# SparkFun_Qwiic_ESLOV_Adapter.net
KiCad netlist of a schematic drawn in EAGLE
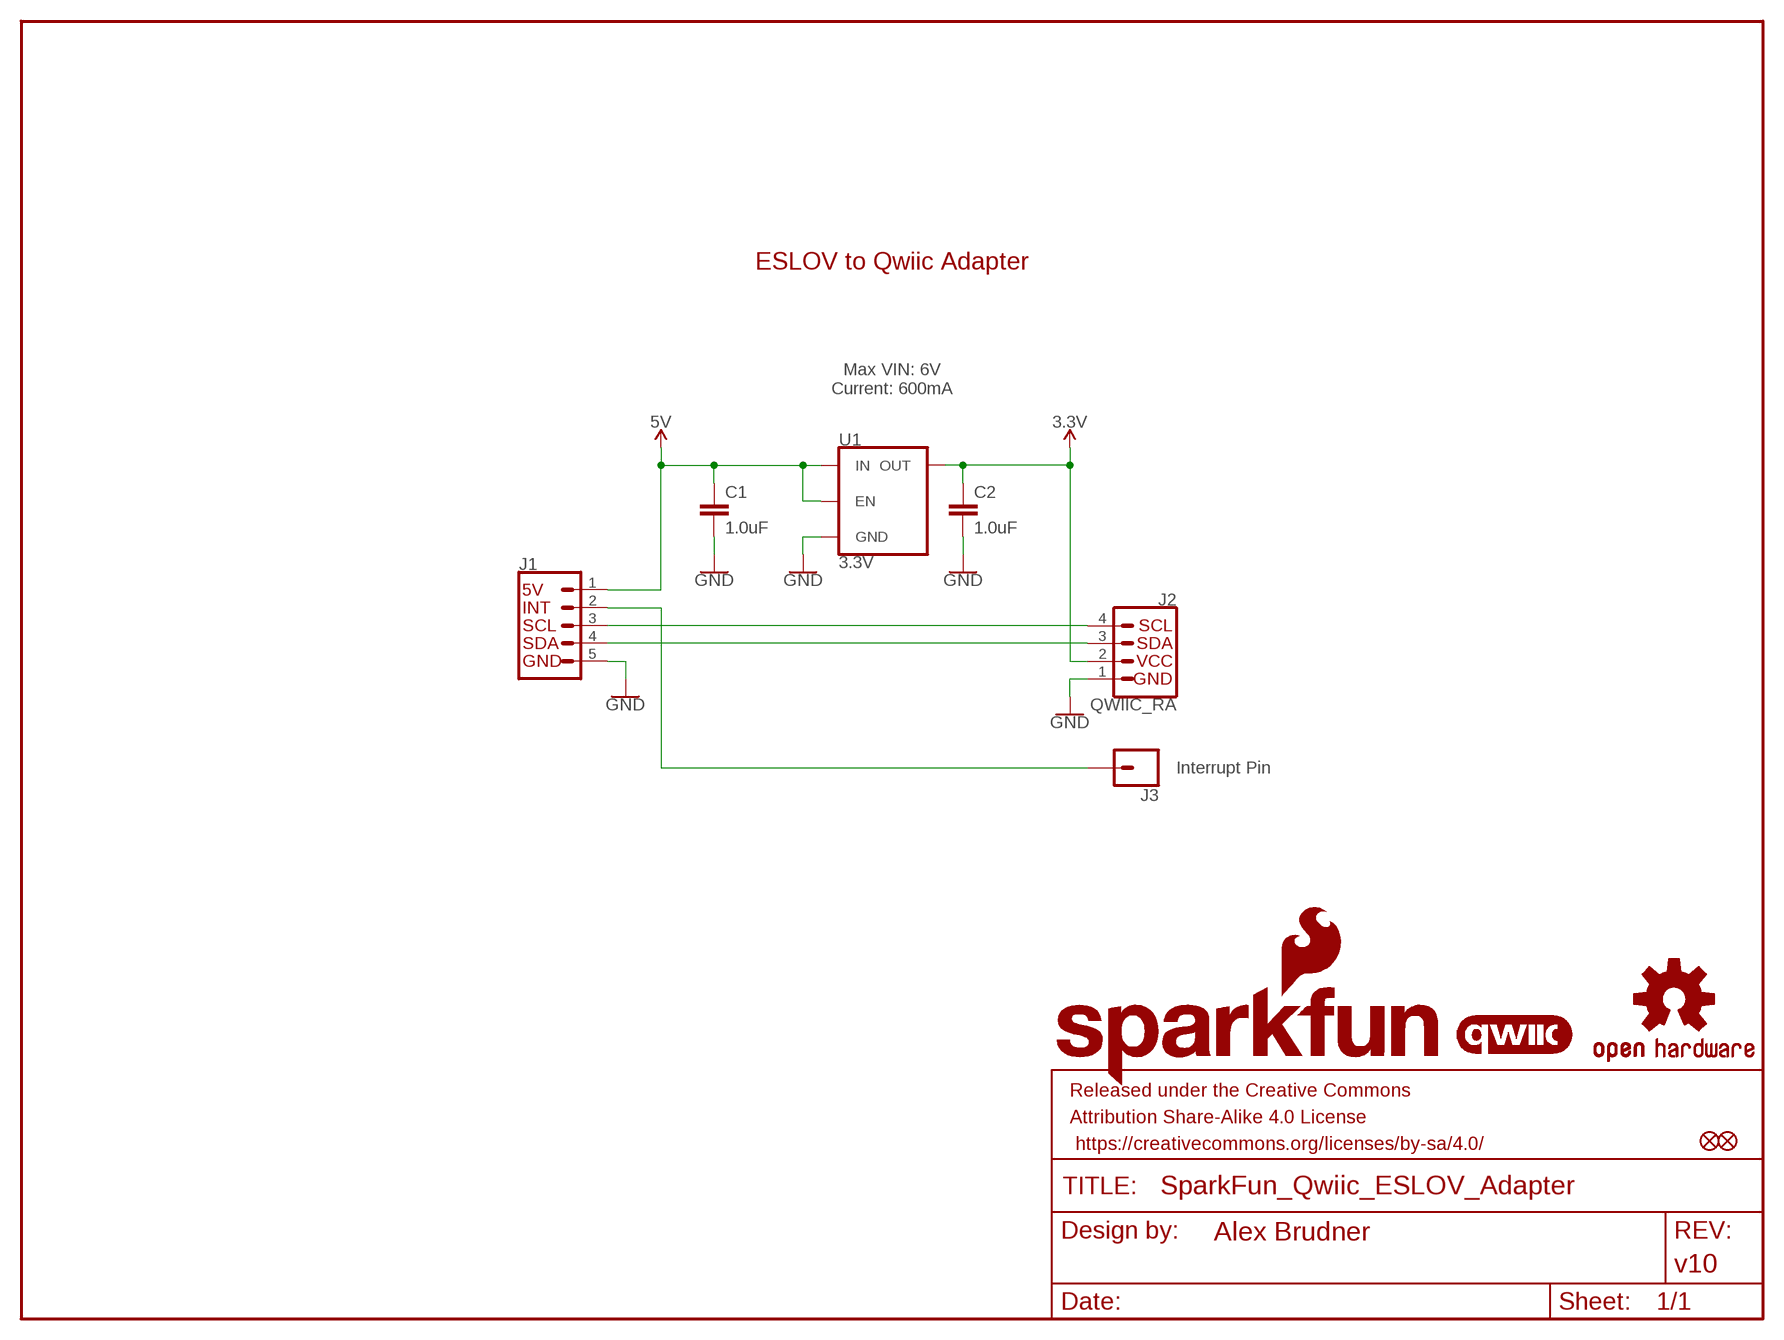
[diagram p0: schematic, sheet 1]

(export (version "E")
  (design (tool "Eeschema 10.0.6"))
  (components
    (comp (ref "C1")
      (value "1.0uF")
      (footprint "eagle-import:0402-TIGHT")
      (libsource (lib "eagle-import") (part "1.0UF-0402T-16V-10%"))
    )
    (comp (ref "C2")
      (value "1.0uF")
      (footprint "eagle-import:0402-TIGHT")
      (libsource (lib "eagle-import") (part "1.0UF-0402T-16V-10%"))
    )
    (comp (ref "FD1")
      (value "FIDUCIALUFIDUCIAL")
      (footprint "eagle-import:FIDUCIAL-MICRO")
      (libsource (lib "eagle-import") (part "FIDUCIALUFIDUCIAL"))
    )
    (comp (ref "FD2")
      (value "FIDUCIALUFIDUCIAL")
      (footprint "eagle-import:FIDUCIAL-MICRO")
      (libsource (lib "eagle-import") (part "FIDUCIALUFIDUCIAL"))
    )
    (comp (ref "FRAME1")
      (value "FRAME-LETTER")
      (footprint "eagle-import:CREATIVE_COMMONS")
      (fields (field (name "DESIGNER") "Alex Brudner") (field (name "REV") "v10"))
      (libsource (lib "eagle-import") (part "FRAME-LETTER"))
    )
    (comp (ref "J1")
      (value "ESLOV")
      (footprint "eagle-import:JST_5_1MM_RA")
      (libsource (lib "eagle-import") (part "ESLOV"))
    )
    (comp (ref "J2")
      (value "QWIIC_RA")
      (footprint "eagle-import:JST04_1MM_RA")
      (libsource (lib "eagle-import") (part "QWIIC_CONNECTORJS-1MM"))
    )
    (comp (ref "J3")
      (value "CONN_01")
      (footprint "eagle-import:1X01")
      (libsource (lib "eagle-import") (part "CONN_01"))
    )
    (comp (ref "LOGO1")
      (value "SFE_LOGO_NAME_FLAME.1_INCH")
      (footprint "eagle-import:SFE_LOGO_NAME_FLAME_.1")
      (libsource (lib "eagle-import") (part "SFE_LOGO_NAME_FLAME.1_INCH"))
    )
    (comp (ref "LOGO2")
      (value "OSHW-LOGOMINI")
      (footprint "eagle-import:OSHW-LOGO-MINI")
      (libsource (lib "eagle-import") (part "OSHW-LOGOMINI"))
    )
    (comp (ref "LOGO3")
      (value "QWIIC_LOGO_CONNECTOR")
      (footprint "eagle-import:QWIIC_5.5MM")
      (libsource (lib "eagle-import") (part "QWIIC_LOGO_CONNECTOR"))
    )
    (comp (ref "U1")
      (value "3.3V")
      (footprint "eagle-import:SOT23-5")
      (libsource (lib "eagle-import") (part "V_REG_AP2112K-3.3V"))
    )
  )
  (nets
    (net (code "1") (name "3.3V") (class "Default")
      (node (ref "C2") (pin "1") (pinfunction "1_1") (pintype "passive"))
      (node (ref "J2") (pin "2") (pinfunction "2_2") (pintype "power_in"))
      (node (ref "U1") (pin "5") (pinfunction "OUT_5") (pintype "passive"))
    )
    (net (code "2") (name "5V") (class "Default")
      (node (ref "C1") (pin "1") (pinfunction "1_1") (pintype "passive"))
      (node (ref "J1") (pin "1") (pinfunction "1_1") (pintype "power_in"))
      (node (ref "U1") (pin "1") (pinfunction "IN_1") (pintype "input"))
      (node (ref "U1") (pin "3") (pinfunction "EN_3") (pintype "input"))
    )
    (net (code "3") (name "GND") (class "Default")
      (node (ref "C1") (pin "2") (pinfunction "2_2") (pintype "passive"))
      (node (ref "C2") (pin "2") (pinfunction "2_2") (pintype "passive"))
      (node (ref "J1") (pin "5") (pinfunction "5_5") (pintype "power_in"))
      (node (ref "J2") (pin "1") (pinfunction "1_1") (pintype "power_in"))
      (node (ref "U1") (pin "2") (pinfunction "GND_2") (pintype "input"))
    )
    (net (code "4") (name "Net-(J1-Pad2)") (class "Default")
      (node (ref "J1") (pin "2") (pinfunction "2_2") (pintype "passive"))
      (node (ref "J3") (pin "1") (pinfunction "1_1") (pintype "passive"))
    )
    (net (code "5") (name "Net-(J1-Pad3)") (class "Default")
      (node (ref "J1") (pin "3") (pinfunction "3_3") (pintype "passive"))
      (node (ref "J2") (pin "4") (pinfunction "4_4") (pintype "passive"))
    )
    (net (code "6") (name "Net-(J1-Pad4)") (class "Default")
      (node (ref "J1") (pin "4") (pinfunction "4_4") (pintype "passive"))
      (node (ref "J2") (pin "3") (pinfunction "3_3") (pintype "passive"))
    )
  )
)
